# ESCD.net
KiCad netlist of a schematic drawn in EAGLE
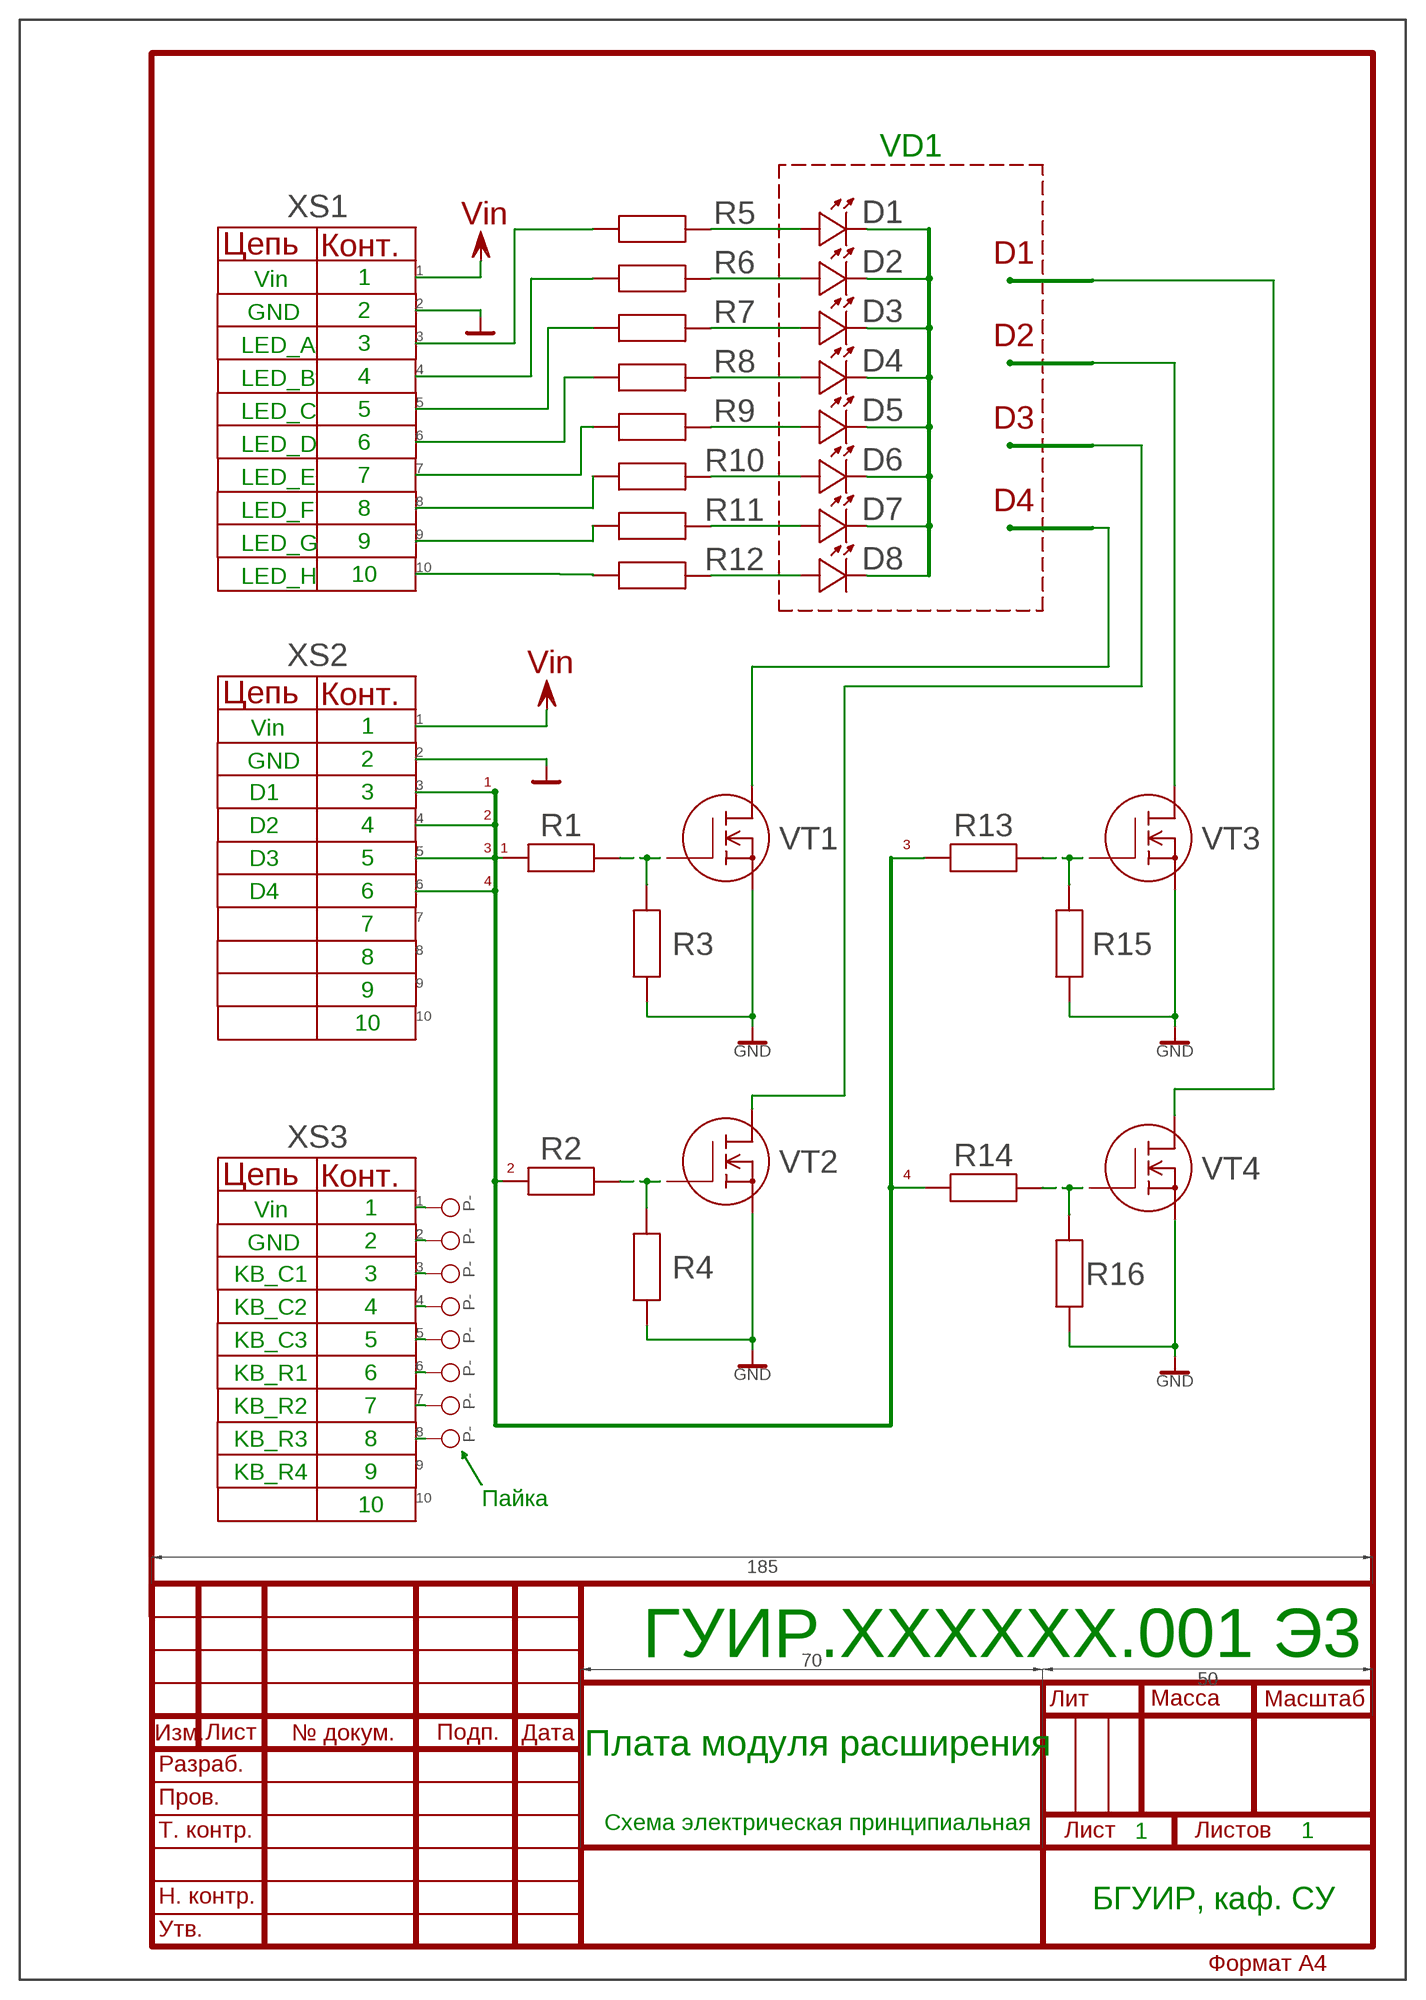
[diagram p0: schematic, sheet 1]

(export (version "E")
  (design (tool "Eeschema 10.0.6"))
  (components
    (comp (ref "D1")
      (value "ESCD_LED")
      (footprint "eagle-import:SOD106A")
      (fields (field (name "MPN") "BYS10/45"))
      (libsource (lib "eagle-import") (part "ESCD_LED"))
    )
    (comp (ref "D2")
      (value "ESCD_LED")
      (footprint "eagle-import:SOD106A")
      (fields (field (name "MPN") "BYS10/45"))
      (libsource (lib "eagle-import") (part "ESCD_LED"))
    )
    (comp (ref "D3")
      (value "ESCD_LED")
      (footprint "eagle-import:SOD106A")
      (fields (field (name "MPN") "BYS10/45"))
      (libsource (lib "eagle-import") (part "ESCD_LED"))
    )
    (comp (ref "D4")
      (value "ESCD_LED")
      (footprint "eagle-import:SOD106A")
      (fields (field (name "MPN") "BYS10/45"))
      (libsource (lib "eagle-import") (part "ESCD_LED"))
    )
    (comp (ref "D5")
      (value "ESCD_LED")
      (footprint "eagle-import:SOD106A")
      (fields (field (name "MPN") "BYS10/45"))
      (libsource (lib "eagle-import") (part "ESCD_LED"))
    )
    (comp (ref "D6")
      (value "ESCD_LED")
      (footprint "eagle-import:SOD106A")
      (fields (field (name "MPN") "BYS10/45"))
      (libsource (lib "eagle-import") (part "ESCD_LED"))
    )
    (comp (ref "D7")
      (value "ESCD_LED")
      (footprint "eagle-import:SOD106A")
      (fields (field (name "MPN") "BYS10/45"))
      (libsource (lib "eagle-import") (part "ESCD_LED"))
    )
    (comp (ref "D8")
      (value "ESCD_LED")
      (footprint "eagle-import:SOD106A")
      (fields (field (name "MPN") "BYS10/45"))
      (libsource (lib "eagle-import") (part "ESCD_LED"))
    )
    (comp (ref "R1")
      (value "ESCD_RES")
      (footprint "eagle-import:R1206")
      (libsource (lib "eagle-import") (part "ESCD_RES"))
    )
    (comp (ref "R2")
      (value "ESCD_RES")
      (footprint "eagle-import:R1206")
      (libsource (lib "eagle-import") (part "ESCD_RES"))
    )
    (comp (ref "R3")
      (value "ESCD_RES")
      (footprint "eagle-import:R1206")
      (libsource (lib "eagle-import") (part "ESCD_RES"))
    )
    (comp (ref "R4")
      (value "ESCD_RES")
      (footprint "eagle-import:R1206")
      (libsource (lib "eagle-import") (part "ESCD_RES"))
    )
    (comp (ref "R5")
      (value "ESCD_RES")
      (footprint "eagle-import:R1206")
      (libsource (lib "eagle-import") (part "ESCD_RES"))
    )
    (comp (ref "R6")
      (value "ESCD_RES")
      (footprint "eagle-import:R1206")
      (libsource (lib "eagle-import") (part "ESCD_RES"))
    )
    (comp (ref "R7")
      (value "ESCD_RES")
      (footprint "eagle-import:R1206")
      (libsource (lib "eagle-import") (part "ESCD_RES"))
    )
    (comp (ref "R8")
      (value "ESCD_RES")
      (footprint "eagle-import:R1206")
      (libsource (lib "eagle-import") (part "ESCD_RES"))
    )
    (comp (ref "R9")
      (value "ESCD_RES")
      (footprint "eagle-import:R1206")
      (libsource (lib "eagle-import") (part "ESCD_RES"))
    )
    (comp (ref "R10")
      (value "ESCD_RES")
      (footprint "eagle-import:R1206")
      (libsource (lib "eagle-import") (part "ESCD_RES"))
    )
    (comp (ref "R11")
      (value "ESCD_RES")
      (footprint "eagle-import:R1206")
      (libsource (lib "eagle-import") (part "ESCD_RES"))
    )
    (comp (ref "R12")
      (value "ESCD_RES")
      (footprint "eagle-import:R1206")
      (libsource (lib "eagle-import") (part "ESCD_RES"))
    )
    (comp (ref "R13")
      (value "ESCD_RES")
      (footprint "eagle-import:R1206")
      (libsource (lib "eagle-import") (part "ESCD_RES"))
    )
    (comp (ref "R14")
      (value "ESCD_RES")
      (footprint "eagle-import:R1206")
      (libsource (lib "eagle-import") (part "ESCD_RES"))
    )
    (comp (ref "R15")
      (value "ESCD_RES")
      (footprint "eagle-import:R1206")
      (libsource (lib "eagle-import") (part "ESCD_RES"))
    )
    (comp (ref "R16")
      (value "ESCD_RES")
      (footprint "eagle-import:R1206")
      (libsource (lib "eagle-import") (part "ESCD_RES"))
    )
    (comp (ref "VT1")
      (value "MOSFET_GOST")
      (footprint "eagle-import:MOSFET")
      (libsource (lib "eagle-import") (part "MOSFET_GOST"))
    )
    (comp (ref "VT2")
      (value "MOSFET_GOST")
      (footprint "eagle-import:MOSFET")
      (libsource (lib "eagle-import") (part "MOSFET_GOST"))
    )
    (comp (ref "VT3")
      (value "MOSFET_GOST")
      (footprint "eagle-import:MOSFET")
      (libsource (lib "eagle-import") (part "MOSFET_GOST"))
    )
    (comp (ref "VT4")
      (value "MOSFET_GOST")
      (footprint "eagle-import:MOSFET")
      (libsource (lib "eagle-import") (part "MOSFET_GOST"))
    )
    (comp (ref "XS1")
      (value "ESCD_CONNECTOR_10POS")
      (footprint "eagle-import:S10B-PH-SM4-TB")
      (libsource (lib "eagle-import") (part "ESCD_CONNECTOR_10POS"))
    )
    (comp (ref "XS2")
      (value "ESCD_CONNECTOR_10POS")
      (footprint "eagle-import:S10B-PH-SM4-TB")
      (libsource (lib "eagle-import") (part "ESCD_CONNECTOR_10POS"))
    )
    (comp (ref "XS3")
      (value "ESCD_CONNECTOR_10POS")
      (footprint "eagle-import:S10B-PH-SM4-TB")
      (libsource (lib "eagle-import") (part "ESCD_CONNECTOR_10POS"))
    )
  )
  (nets
    (net (code "1") (name "GND") (class "Default")
      (node (ref "R15") (pin "1") (pinfunction "1_1") (pintype "passive"))
      (node (ref "R16") (pin "1") (pinfunction "1_1") (pintype "passive"))
      (node (ref "R3") (pin "1") (pinfunction "1_1") (pintype "passive"))
      (node (ref "R4") (pin "1") (pinfunction "1_1") (pintype "passive"))
      (node (ref "VT1") (pin "P$1") (pinfunction "P$1_P$1") (pintype "bidirectional"))
      (node (ref "VT2") (pin "P$1") (pinfunction "P$1_P$1") (pintype "bidirectional"))
      (node (ref "VT3") (pin "P$1") (pinfunction "P$1_P$1") (pintype "bidirectional"))
      (node (ref "VT4") (pin "P$1") (pinfunction "P$1_P$1") (pintype "bidirectional"))
      (node (ref "XS1") (pin "2") (pinfunction "2_2") (pintype "passive"))
      (node (ref "XS2") (pin "2") (pinfunction "2_2") (pintype "passive"))
    )
    (net (code "2") (name "Net-(D1-PadA)") (class "Default")
      (node (ref "D1") (pin "A") (pinfunction "A_A") (pintype "passive"))
      (node (ref "R5") (pin "1") (pinfunction "1_1") (pintype "passive"))
    )
    (net (code "3") (name "Net-(D2-PadA)") (class "Default")
      (node (ref "D2") (pin "A") (pinfunction "A_A") (pintype "passive"))
      (node (ref "R6") (pin "1") (pinfunction "1_1") (pintype "passive"))
    )
    (net (code "4") (name "Net-(D3-PadA)") (class "Default")
      (node (ref "D3") (pin "A") (pinfunction "A_A") (pintype "passive"))
      (node (ref "R7") (pin "1") (pinfunction "1_1") (pintype "passive"))
    )
    (net (code "5") (name "Net-(D4-PadA)") (class "Default")
      (node (ref "D4") (pin "A") (pinfunction "A_A") (pintype "passive"))
      (node (ref "R8") (pin "1") (pinfunction "1_1") (pintype "passive"))
    )
    (net (code "6") (name "Net-(D5-PadA)") (class "Default")
      (node (ref "D5") (pin "A") (pinfunction "A_A") (pintype "passive"))
      (node (ref "R9") (pin "1") (pinfunction "1_1") (pintype "passive"))
    )
    (net (code "7") (name "Net-(D6-PadA)") (class "Default")
      (node (ref "D6") (pin "A") (pinfunction "A_A") (pintype "passive"))
      (node (ref "R10") (pin "1") (pinfunction "1_1") (pintype "passive"))
    )
    (net (code "8") (name "Net-(D7-PadA)") (class "Default")
      (node (ref "D7") (pin "A") (pinfunction "A_A") (pintype "passive"))
      (node (ref "R11") (pin "1") (pinfunction "1_1") (pintype "passive"))
    )
    (net (code "9") (name "Net-(D8-PadA)") (class "Default")
      (node (ref "D8") (pin "A") (pinfunction "A_A") (pintype "passive"))
      (node (ref "R12") (pin "1") (pinfunction "1_1") (pintype "passive"))
    )
    (net (code "10") (name "Net-(R1-Pad1)") (class "Default")
      (node (ref "R1") (pin "1") (pinfunction "1_1") (pintype "passive"))
      (node (ref "R13") (pin "1") (pinfunction "1_1") (pintype "passive"))
      (node (ref "R14") (pin "1") (pinfunction "1_1") (pintype "passive"))
      (node (ref "R2") (pin "1") (pinfunction "1_1") (pintype "passive"))
      (node (ref "XS2") (pin "3") (pinfunction "3_3") (pintype "passive"))
      (node (ref "XS2") (pin "4") (pinfunction "4_4") (pintype "passive"))
      (node (ref "XS2") (pin "5") (pinfunction "5_5") (pintype "passive"))
      (node (ref "XS2") (pin "6") (pinfunction "6_6") (pintype "passive"))
    )
    (net (code "11") (name "Net-(R1-Pad2)") (class "Default")
      (node (ref "R1") (pin "2") (pinfunction "2_2") (pintype "passive"))
      (node (ref "R3") (pin "2") (pinfunction "2_2") (pintype "passive"))
      (node (ref "VT1") (pin "P$3") (pinfunction "P$3_P$3") (pintype "bidirectional"))
    )
    (net (code "12") (name "Net-(R2-Pad2)") (class "Default")
      (node (ref "R2") (pin "2") (pinfunction "2_2") (pintype "passive"))
      (node (ref "R4") (pin "2") (pinfunction "2_2") (pintype "passive"))
      (node (ref "VT2") (pin "P$3") (pinfunction "P$3_P$3") (pintype "bidirectional"))
    )
    (net (code "13") (name "Net-(R5-Pad2)") (class "Default")
      (node (ref "R5") (pin "2") (pinfunction "2_2") (pintype "passive"))
      (node (ref "XS1") (pin "3") (pinfunction "3_3") (pintype "passive"))
    )
    (net (code "14") (name "Net-(R6-Pad2)") (class "Default")
      (node (ref "R6") (pin "2") (pinfunction "2_2") (pintype "passive"))
      (node (ref "XS1") (pin "4") (pinfunction "4_4") (pintype "passive"))
    )
    (net (code "15") (name "Net-(R7-Pad2)") (class "Default")
      (node (ref "R7") (pin "2") (pinfunction "2_2") (pintype "passive"))
      (node (ref "XS1") (pin "5") (pinfunction "5_5") (pintype "passive"))
    )
    (net (code "16") (name "Net-(R8-Pad2)") (class "Default")
      (node (ref "R8") (pin "2") (pinfunction "2_2") (pintype "passive"))
      (node (ref "XS1") (pin "6") (pinfunction "6_6") (pintype "passive"))
    )
    (net (code "17") (name "Net-(R9-Pad2)") (class "Default")
      (node (ref "R9") (pin "2") (pinfunction "2_2") (pintype "passive"))
      (node (ref "XS1") (pin "7") (pinfunction "7_7") (pintype "passive"))
    )
    (net (code "18") (name "Net-(R10-Pad2)") (class "Default")
      (node (ref "R10") (pin "2") (pinfunction "2_2") (pintype "passive"))
      (node (ref "XS1") (pin "8") (pinfunction "8_8") (pintype "passive"))
    )
    (net (code "19") (name "Net-(R11-Pad2)") (class "Default")
      (node (ref "R11") (pin "2") (pinfunction "2_2") (pintype "passive"))
      (node (ref "XS1") (pin "9") (pinfunction "9_9") (pintype "passive"))
    )
    (net (code "20") (name "Net-(R13-Pad2)") (class "Default")
      (node (ref "R13") (pin "2") (pinfunction "2_2") (pintype "passive"))
      (node (ref "R15") (pin "2") (pinfunction "2_2") (pintype "passive"))
      (node (ref "VT3") (pin "P$3") (pinfunction "P$3_P$3") (pintype "bidirectional"))
    )
    (net (code "21") (name "Net-(R14-Pad2)") (class "Default")
      (node (ref "R14") (pin "2") (pinfunction "2_2") (pintype "passive"))
      (node (ref "R16") (pin "2") (pinfunction "2_2") (pintype "passive"))
      (node (ref "VT4") (pin "P$3") (pinfunction "P$3_P$3") (pintype "bidirectional"))
    )
    (net (code "22") (name "P-") (class "Default")
      (node (ref "XS1") (pin "1") (pinfunction "1_1") (pintype "passive"))
      (node (ref "XS2") (pin "1") (pinfunction "1_1") (pintype "passive"))
      (node (ref "XS3") (pin "1") (pinfunction "1_1") (pintype "passive"))
      (node (ref "XS3") (pin "2") (pinfunction "2_2") (pintype "passive"))
      (node (ref "XS3") (pin "3") (pinfunction "3_3") (pintype "passive"))
      (node (ref "XS3") (pin "4") (pinfunction "4_4") (pintype "passive"))
      (node (ref "XS3") (pin "5") (pinfunction "5_5") (pintype "passive"))
      (node (ref "XS3") (pin "6") (pinfunction "6_6") (pintype "passive"))
      (node (ref "XS3") (pin "7") (pinfunction "7_7") (pintype "passive"))
      (node (ref "XS3") (pin "8") (pinfunction "8_8") (pintype "passive"))
    )
    (net (code "23") (name "unconnected-(D1-PadK)") (class "Default")
      (node (ref "D1") (pin "K") (pinfunction "K_K") (pintype "passive"))
    )
    (net (code "24") (name "unconnected-(D2-PadK)") (class "Default")
      (node (ref "D2") (pin "K") (pinfunction "K_K") (pintype "passive"))
    )
    (net (code "25") (name "unconnected-(D3-PadK)") (class "Default")
      (node (ref "D3") (pin "K") (pinfunction "K_K") (pintype "passive"))
    )
    (net (code "26") (name "unconnected-(D4-PadK)") (class "Default")
      (node (ref "D4") (pin "K") (pinfunction "K_K") (pintype "passive"))
    )
    (net (code "27") (name "unconnected-(D5-PadK)") (class "Default")
      (node (ref "D5") (pin "K") (pinfunction "K_K") (pintype "passive"))
    )
    (net (code "28") (name "unconnected-(D6-PadK)") (class "Default")
      (node (ref "D6") (pin "K") (pinfunction "K_K") (pintype "passive"))
    )
    (net (code "29") (name "unconnected-(D7-PadK)") (class "Default")
      (node (ref "D7") (pin "K") (pinfunction "K_K") (pintype "passive"))
    )
    (net (code "30") (name "unconnected-(D8-PadK)") (class "Default")
      (node (ref "D8") (pin "K") (pinfunction "K_K") (pintype "passive"))
    )
    (net (code "31") (name "unconnected-(R12-Pad2)") (class "Default")
      (node (ref "R12") (pin "2") (pinfunction "2_2") (pintype "passive"))
    )
    (net (code "32") (name "unconnected-(VT1-PadP$2)") (class "Default")
      (node (ref "VT1") (pin "P$2") (pinfunction "P$2_P$2") (pintype "bidirectional"))
    )
    (net (code "33") (name "unconnected-(VT2-PadP$2)") (class "Default")
      (node (ref "VT2") (pin "P$2") (pinfunction "P$2_P$2") (pintype "bidirectional"))
    )
    (net (code "34") (name "unconnected-(VT3-PadP$2)") (class "Default")
      (node (ref "VT3") (pin "P$2") (pinfunction "P$2_P$2") (pintype "bidirectional"))
    )
    (net (code "35") (name "unconnected-(VT4-PadP$2)") (class "Default")
      (node (ref "VT4") (pin "P$2") (pinfunction "P$2_P$2") (pintype "bidirectional"))
    )
    (net (code "36") (name "unconnected-(XS1-Pad10)") (class "Default")
      (node (ref "XS1") (pin "10") (pinfunction "10_10") (pintype "passive"))
    )
    (net (code "37") (name "unconnected-(XS2-Pad7)") (class "Default")
      (node (ref "XS2") (pin "7") (pinfunction "7_7") (pintype "passive"))
    )
    (net (code "38") (name "unconnected-(XS2-Pad8)") (class "Default")
      (node (ref "XS2") (pin "8") (pinfunction "8_8") (pintype "passive"))
    )
    (net (code "39") (name "unconnected-(XS2-Pad9)") (class "Default")
      (node (ref "XS2") (pin "9") (pinfunction "9_9") (pintype "passive"))
    )
    (net (code "40") (name "unconnected-(XS2-Pad10)") (class "Default")
      (node (ref "XS2") (pin "10") (pinfunction "10_10") (pintype "passive"))
    )
    (net (code "41") (name "unconnected-(XS3-Pad9)") (class "Default")
      (node (ref "XS3") (pin "9") (pinfunction "9_9") (pintype "passive"))
    )
    (net (code "42") (name "unconnected-(XS3-Pad10)") (class "Default")
      (node (ref "XS3") (pin "10") (pinfunction "10_10") (pintype "passive"))
    )
  )
)
